# khoinguon.net
KiCad netlist of a schematic drawn in Altium Designer
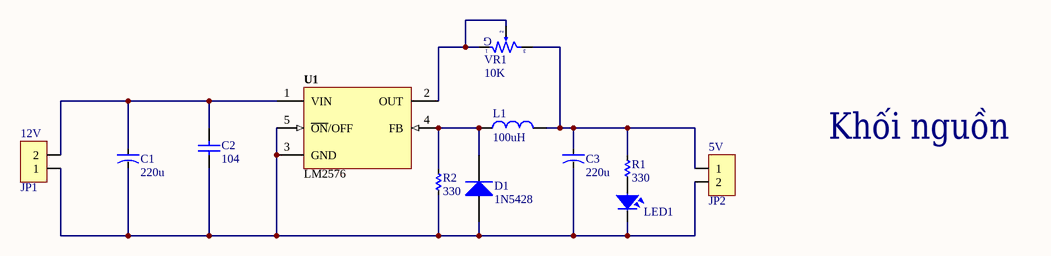
[diagram p0: khoinguon.SchDoc]

(export (version "E")
  (design (tool "Eeschema 10.0.6"))
  (components
    (comp (ref "5V")
      (value "JP2")
      (footprint "JP2-C1T")
      (description "WR-PHD 2.54 mm Angled Socket Header")
      (fields
        (field (name "MANUFACTURER") "Würth Elektronik eiSos GmbH")
        (field (name "PARTNO") "613002143121")
        (field (name "CREATED BY") "Karrer Zheng")
      )
      (libsource (lib "") (part "JP2_1"))
    )
    (comp (ref "12V")
      (value "JP1")
      (footprint "JP2-C1T")
      (description "WR-PHD 2.54 mm Angled Socket Header")
      (fields
        (field (name "MANUFACTURER") "Würth Elektronik eiSos GmbH")
        (field (name "PARTNO") "613002143121")
        (field (name "CREATED BY") "Karrer Zheng")
      )
      (libsource (lib "Altium Library") (part "JP2"))
    )
    (comp (ref "C1")
      (value "220u")
      (footprint "CA-ALU-2.54")
      (description "Capacitor (Semiconductor SIM Model)")
      (fields (field (name "PUBLISHER") "Altium Limited"))
      (libsource (lib "Altium Library") (part "CN-ALU-DIP"))
    )
    (comp (ref "C2")
      (value "104")
      (footprint "103/2KV")
      (fields (field (name "PUBLISHER") "Altium Limited"))
      (libsource (lib "Schematic") (part "Cap2KV"))
    )
    (comp (ref "C3")
      (value "220u")
      (footprint "CA-ALU-2.54")
      (description "Capacitor (Semiconductor SIM Model)")
      (fields (field (name "PUBLISHER") "Altium Limited"))
      (libsource (lib "Altium Library") (part "CN-ALU-DIP"))
    )
    (comp (ref "D1")
      (value "1N5428")
      (footprint "DIODE/POW/1A")
      (description "Diode Power")
      (fields (field (name "PUBLISHER") "Altium Limited"))
      (libsource (lib "Schematic") (part "Diode Power"))
    )
    (comp (ref "L1")
      (value "100uH")
      (footprint "L01")
      (description "Inductor")
      (libsource (lib "Cty1") (part "L1"))
    )
    (comp (ref "LED1")
      (value "LED")
      (footprint "LED-3MM-YELLOW")
      (description "LED Single colour Green and Red")
      (libsource (lib "Altium Library") (part "LED"))
    )
    (comp (ref "R1")
      (value "330")
      (footprint "RES-1/2W")
      (description "Res")
      (fields
        (field (name "MANUFACTURER") "Generic Components")
        (field (name "PUBLISHER") "Altium Hobart Technology Centre")
      )
      (libsource (lib "Altium Library") (part "Res"))
    )
    (comp (ref "R2")
      (value "330")
      (footprint "RES-1/2W")
      (description "Res")
      (fields
        (field (name "MANUFACTURER") "Generic Components")
        (field (name "PUBLISHER") "Altium Hobart Technology Centre")
      )
      (libsource (lib "Altium Library") (part "Res"))
    )
    (comp (ref "U1") (value "LM2576") (footprint "DIP5-T") (libsource (lib "Altium Library") (part "LM2576")))
    (comp (ref "VR1")
      (value "10K")
      (footprint "VR-S1")
      (description "Var Resistor")
      (libsource (lib "Altium Library") (part "VR-S"))
    )
  )
  (nets
    (net (code "1") (name "Net-(5V-Pad1)") (class "Default")
      (node (ref "5V") (pin "1") (pinfunction "1_1") (pintype "passive"))
      (node (ref "C3") (pin "1") (pinfunction "1_1") (pintype "passive"))
      (node (ref "L1") (pin "2") (pinfunction "2_2") (pintype "passive"))
      (node (ref "R1") (pin "2") (pinfunction "2_2") (pintype "passive"))
      (node (ref "VR1") (pin "3") (pinfunction "3_3") (pintype "passive"))
    )
    (net (code "2") (name "Net-(D1-A)") (class "Default")
      (node (ref "12V") (pin "1") (pinfunction "1_1") (pintype "passive"))
      (node (ref "5V") (pin "2") (pinfunction "2_2") (pintype "passive"))
      (node (ref "C1") (pin "2") (pinfunction "2_2") (pintype "passive"))
      (node (ref "C2") (pin "2") (pinfunction "2_2") (pintype "passive"))
      (node (ref "C3") (pin "2") (pinfunction "2_2") (pintype "passive"))
      (node (ref "D1") (pin "1") (pinfunction "A_1") (pintype "passive"))
      (node (ref "LED1") (pin "2") (pinfunction "2_2") (pintype "passive"))
      (node (ref "R2") (pin "1") (pinfunction "1_1") (pintype "passive"))
      (node (ref "U1") (pin "3") (pinfunction "GND_3") (pintype "power_in"))
      (node (ref "U1") (pin "5") (pinfunction "~{ON}/OFF_5") (pintype "input"))
    )
    (net (code "3") (name "Net-(D1-K)") (class "Default")
      (node (ref "D1") (pin "2") (pinfunction "K_2") (pintype "passive"))
      (node (ref "L1") (pin "1") (pinfunction "1_1") (pintype "passive"))
      (node (ref "R2") (pin "2") (pinfunction "2_2") (pintype "passive"))
      (node (ref "U1") (pin "4") (pinfunction "FB_4") (pintype "input"))
    )
    (net (code "4") (name "Net-(LED1-Pad1)") (class "Default")
      (node (ref "LED1") (pin "1") (pinfunction "1_1") (pintype "passive"))
      (node (ref "R1") (pin "1") (pinfunction "1_1") (pintype "passive"))
    )
    (net (code "5") (name "Net-(U1-OUT)") (class "Default")
      (node (ref "U1") (pin "2") (pinfunction "OUT_2") (pintype "power_in"))
      (node (ref "VR1") (pin "1") (pinfunction "1_1") (pintype "passive"))
      (node (ref "VR1") (pin "2") (pinfunction "2_2") (pintype "passive"))
    )
    (net (code "6") (name "Net-(U1-VIN)") (class "Default")
      (node (ref "12V") (pin "2") (pinfunction "2_2") (pintype "passive"))
      (node (ref "C1") (pin "1") (pinfunction "1_1") (pintype "passive"))
      (node (ref "C2") (pin "1") (pinfunction "1_1") (pintype "passive"))
      (node (ref "U1") (pin "1") (pinfunction "VIN_1") (pintype "power_in"))
    )
  )
)
